# RPI.net
KiCad netlist of a schematic drawn in Altium Designer
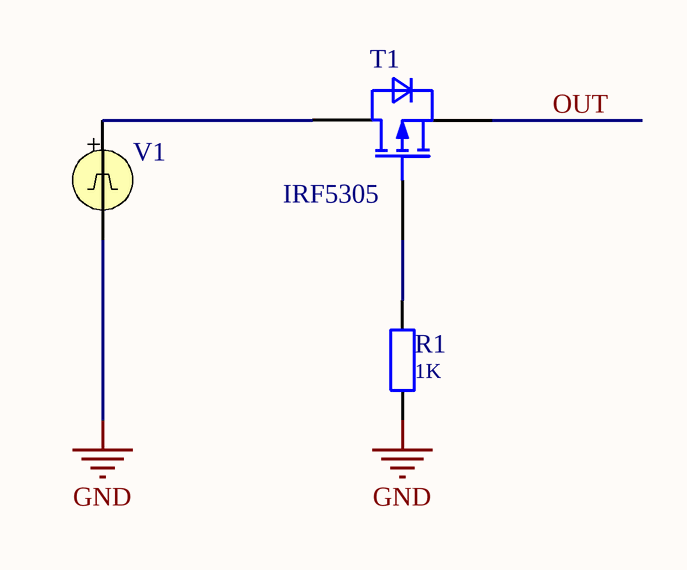
[diagram p0: RPI.SchDoc]

(export (version "E")
  (design (tool "Eeschema 10.0.6"))
  (components
    (comp (ref "R1")
      (value "1K")
      (footprint "R_0207/RM4")
      (description "Resistor")
      (libsource (lib "HTLInn_RLCQ") (part "R"))
    )
    (comp (ref "T1")
      (value "IRF5305")
      (footprint "PG-TO220-3-904")
      (description "OptiMOS - P2 Power-Transistor, P-channel-Enhancement mode, VDS -30V")
      (libsource (lib "MOSFET_HBridge") (part "IRF5305"))
    )
    (comp (ref "V1")
      (value "PULSE(0 5 0 1u 1u 0.5ms 1ms)")
      (description "Pulse Voltage Source")
      (libsource (lib "HTLinn_Sources") (part "VPULSE"))
    )
  )
  (nets
    (net (code "1") (name "/OUT") (class "Default")
      (node (ref "T1") (pin "3") (pinfunction "DRAIN_3") (pintype "passive"))
    )
    (net (code "2") (name "GND") (class "Default")
      (node (ref "R1") (pin "1") (pinfunction "1_1") (pintype "passive"))
      (node (ref "V1") (pin "2") (pinfunction "2_2") (pintype "passive"))
    )
    (net (code "3") (name "Net-(T1-GATE)") (class "Default")
      (node (ref "R1") (pin "2") (pinfunction "2_2") (pintype "passive"))
      (node (ref "T1") (pin "1") (pinfunction "GATE_1") (pintype "passive"))
    )
    (net (code "4") (name "Net-(T1-SOURCE)") (class "Default")
      (node (ref "T1") (pin "2") (pinfunction "SOURCE_2") (pintype "passive"))
      (node (ref "V1") (pin "1") (pinfunction "1_1") (pintype "passive"))
    )
  )
)
